# moth_v2_1.net
KiCad netlist of a schematic drawn in EAGLE
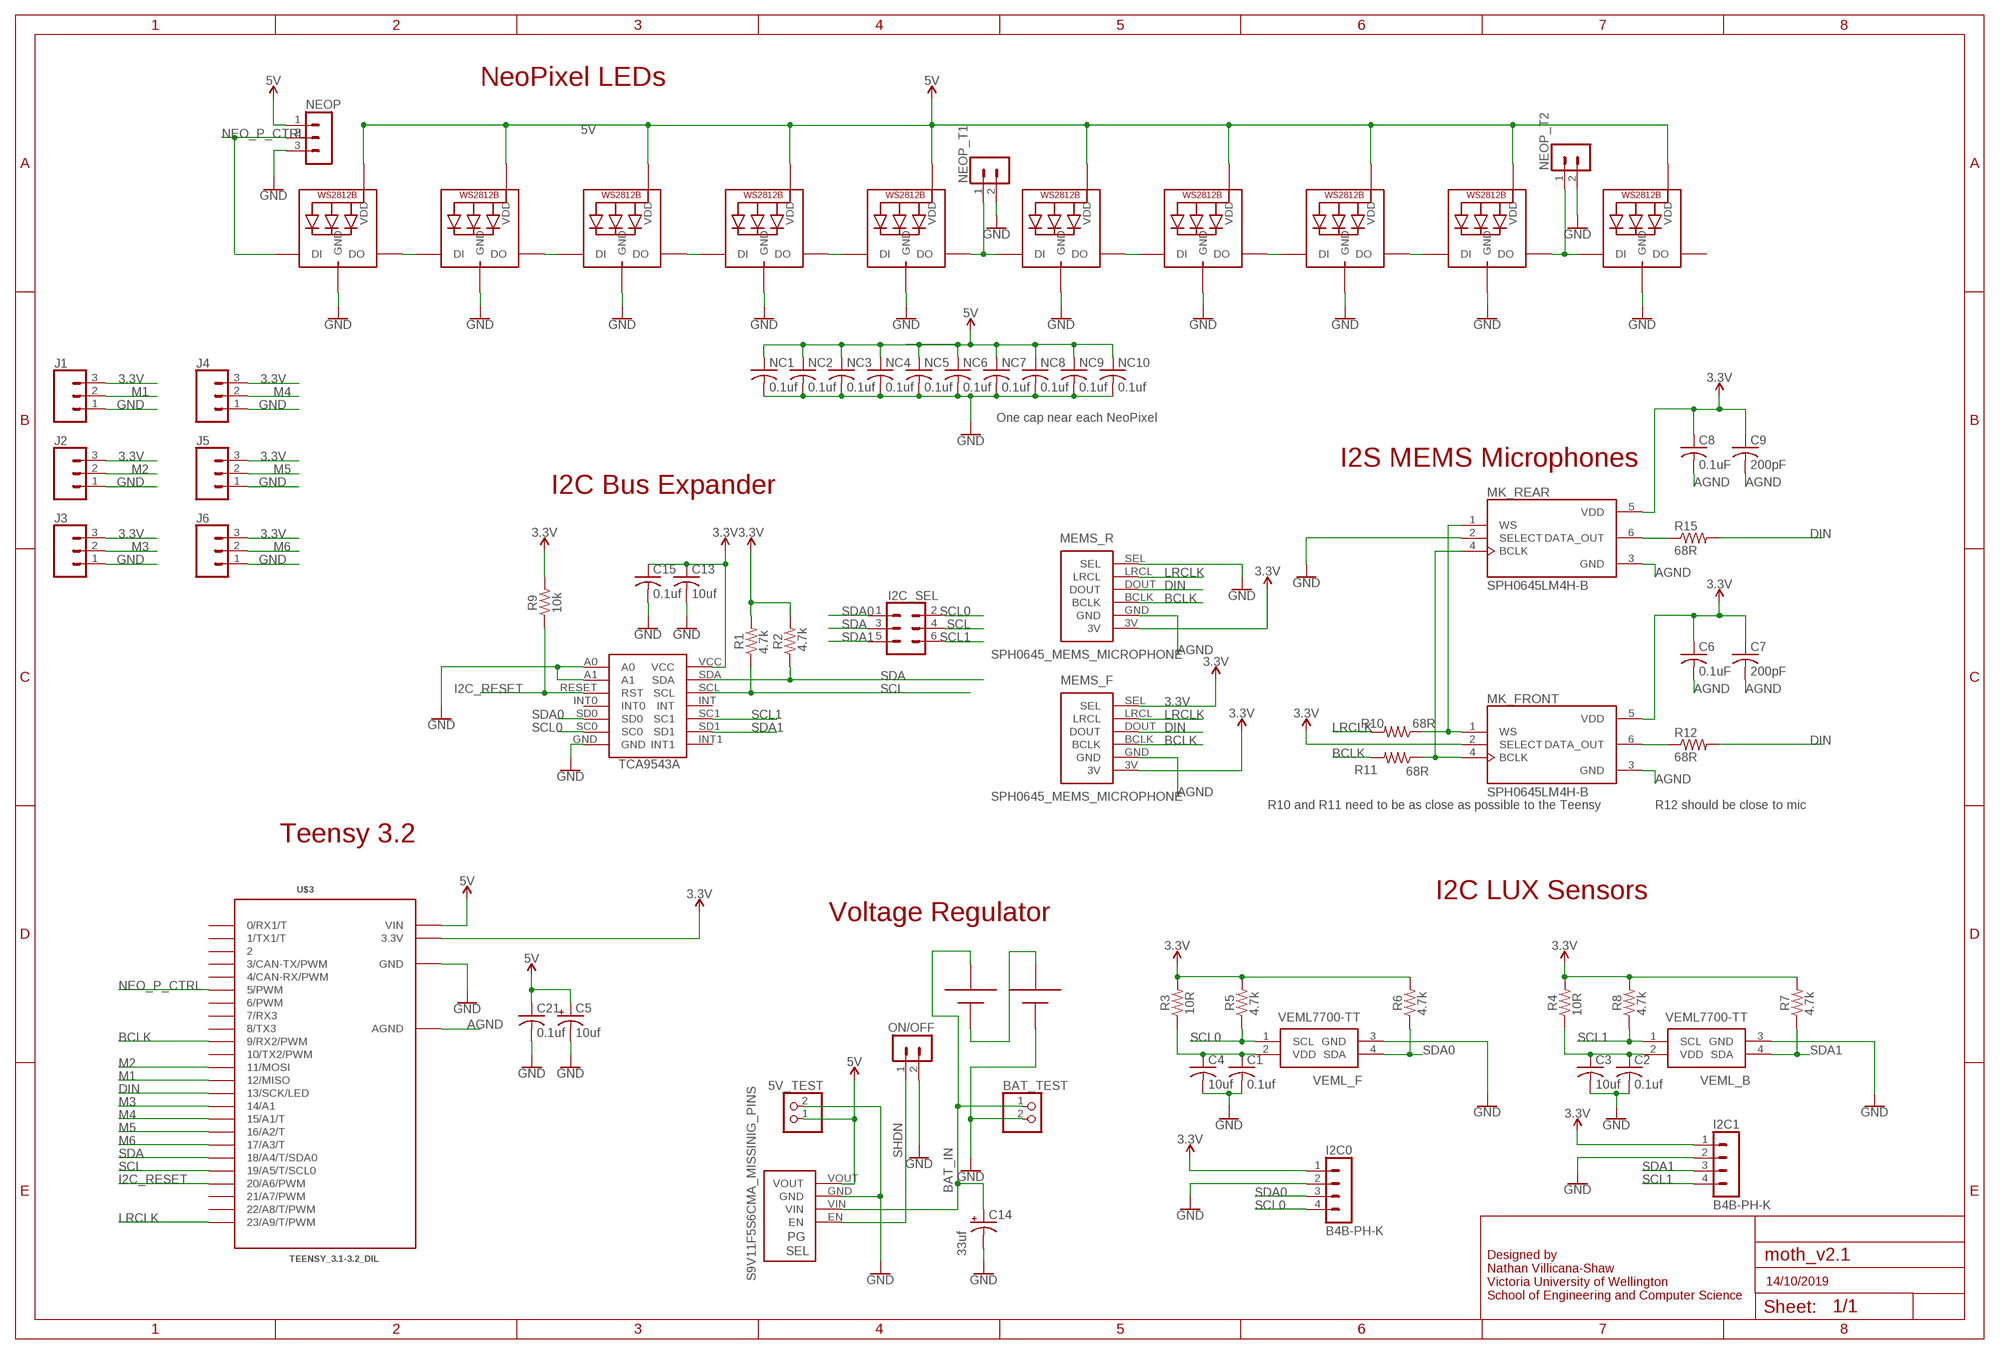
[diagram p0: schematic, sheet 1]

(export (version "E")
  (design (tool "Eeschema 10.0.6"))
  (components
    (comp (ref "5V_TEST")
      (value "PINHD-1X2")
      (footprint "eagle-import:1X02")
      (libsource (lib "eagle-import") (part "PINHD-1X2"))
    )
    (comp (ref "BAT_TEST")
      (value "PINHD-1X2")
      (footprint "eagle-import:1X02")
      (libsource (lib "eagle-import") (part "PINHD-1X2"))
    )
    (comp (ref "C1")
      (value "0.1uf")
      (footprint "eagle-import:C1206K")
      (libsource (lib "eagle-import") (part "C-USC1206K"))
    )
    (comp (ref "C2")
      (value "0.1uf")
      (footprint "eagle-import:C1206K")
      (libsource (lib "eagle-import") (part "C-USC1206K"))
    )
    (comp (ref "C3")
      (value "10uf")
      (footprint "eagle-import:C1206K")
      (libsource (lib "eagle-import") (part "C-USC1206K"))
    )
    (comp (ref "C4")
      (value "10uf")
      (footprint "eagle-import:C1206K")
      (libsource (lib "eagle-import") (part "C-USC1206K"))
    )
    (comp (ref "C5")
      (value "10uf")
      (footprint "eagle-import:E2,5-6")
      (libsource (lib "eagle-import") (part "CPOL-USE2.5-6"))
    )
    (comp (ref "C6")
      (value "0.1uF")
      (footprint "eagle-import:C1206K")
      (libsource (lib "eagle-import") (part "C-USC1206K"))
    )
    (comp (ref "C7")
      (value "200pF")
      (footprint "eagle-import:C1206K")
      (libsource (lib "eagle-import") (part "C-USC1206K"))
    )
    (comp (ref "C8")
      (value "0.1uF")
      (footprint "eagle-import:C1206K")
      (libsource (lib "eagle-import") (part "C-USC1206K"))
    )
    (comp (ref "C9")
      (value "200pF")
      (footprint "eagle-import:C1206K")
      (libsource (lib "eagle-import") (part "C-USC1206K"))
    )
    (comp (ref "C13")
      (value "10uf")
      (footprint "eagle-import:C1206K")
      (libsource (lib "eagle-import") (part "C-USC1206K"))
    )
    (comp (ref "C14")
      (value "33uf")
      (footprint "eagle-import:E2-5")
      (libsource (lib "eagle-import") (part "CPOL-USE2-5"))
    )
    (comp (ref "C15")
      (value "0.1uf")
      (footprint "eagle-import:C1206K")
      (libsource (lib "eagle-import") (part "C-USC1206K"))
    )
    (comp (ref "C21")
      (value "0.1uf")
      (footprint "eagle-import:C1206K")
      (libsource (lib "eagle-import") (part "C-USC1206K"))
    )
    (comp (ref "I2C0")
      (value "B4B-PH-K")
      (footprint "eagle-import:B4B-PH-K")
      (libsource (lib "eagle-import") (part "B4B-PH-K"))
    )
    (comp (ref "I2C1")
      (value "B4B-PH-K")
      (footprint "eagle-import:B4B-PH-K")
      (libsource (lib "eagle-import") (part "B4B-PH-K"))
    )
    (comp (ref "I2C_SEL")
      (value "FEMALE 2x3")
      (footprint "eagle-import:2X3")
      (libsource (lib "eagle-import") (part "CONN_03X2FEMALE"))
    )
    (comp (ref "J1")
      (value "CONN_03")
      (footprint "eagle-import:1X03")
      (libsource (lib "eagle-import") (part "CONN_03"))
    )
    (comp (ref "J2")
      (value "CONN_03")
      (footprint "eagle-import:1X03")
      (libsource (lib "eagle-import") (part "CONN_03"))
    )
    (comp (ref "J3")
      (value "CONN_03")
      (footprint "eagle-import:1X03")
      (libsource (lib "eagle-import") (part "CONN_03"))
    )
    (comp (ref "J4")
      (value "CONN_03")
      (footprint "eagle-import:1X03")
      (libsource (lib "eagle-import") (part "CONN_03"))
    )
    (comp (ref "J5")
      (value "CONN_03")
      (footprint "eagle-import:1X03")
      (libsource (lib "eagle-import") (part "CONN_03"))
    )
    (comp (ref "J6")
      (value "CONN_03")
      (footprint "eagle-import:1X03")
      (libsource (lib "eagle-import") (part "CONN_03"))
    )
    (comp (ref "MEMS_F")
      (value "SPH0645_MEMS_MICROPHONE")
      (footprint "eagle-import:SPH0645")
      (libsource (lib "eagle-import") (part "SPH0645_MEMS_MICROPHONE"))
    )
    (comp (ref "MEMS_R")
      (value "SPH0645_MEMS_MICROPHONE")
      (footprint "eagle-import:SPH0645")
      (libsource (lib "eagle-import") (part "SPH0645_MEMS_MICROPHONE"))
    )
    (comp (ref "MK_FRONT")
      (value "SPH0645LM4H-B")
      (footprint "eagle-import:MIC_SPH0645LM4H-B")
      (fields (field (name "DIGI-KEY_PART_NUMBER") "423-1405-1-ND") (field (name "MF") "Knowles"))
      (libsource (lib "eagle-import") (part "SPH0645LM4H-B"))
    )
    (comp (ref "MK_REAR")
      (value "SPH0645LM4H-B")
      (footprint "eagle-import:MIC_SPH0645LM4H-B")
      (fields (field (name "DIGI-KEY_PART_NUMBER") "423-1405-1-ND") (field (name "MF") "Knowles"))
      (libsource (lib "eagle-import") (part "SPH0645LM4H-B"))
    )
    (comp (ref "NC1")
      (value "0.1uf")
      (footprint "eagle-import:C1206K")
      (libsource (lib "eagle-import") (part "C-USC1206K"))
    )
    (comp (ref "NC2")
      (value "0.1uf")
      (footprint "eagle-import:C1206K")
      (libsource (lib "eagle-import") (part "C-USC1206K"))
    )
    (comp (ref "NC3")
      (value "0.1uf")
      (footprint "eagle-import:C1206K")
      (libsource (lib "eagle-import") (part "C-USC1206K"))
    )
    (comp (ref "NC4")
      (value "0.1uf")
      (footprint "eagle-import:C1206K")
      (libsource (lib "eagle-import") (part "C-USC1206K"))
    )
    (comp (ref "NC5")
      (value "0.1uf")
      (footprint "eagle-import:C1206K")
      (libsource (lib "eagle-import") (part "C-USC1206K"))
    )
    (comp (ref "NC6")
      (value "0.1uf")
      (footprint "eagle-import:C1206K")
      (libsource (lib "eagle-import") (part "C-USC1206K"))
    )
    (comp (ref "NC7")
      (value "0.1uf")
      (footprint "eagle-import:C1206K")
      (libsource (lib "eagle-import") (part "C-USC1206K"))
    )
    (comp (ref "NC8")
      (value "0.1uf")
      (footprint "eagle-import:C1206K")
      (libsource (lib "eagle-import") (part "C-USC1206K"))
    )
    (comp (ref "NC9")
      (value "0.1uf")
      (footprint "eagle-import:C1206K")
      (libsource (lib "eagle-import") (part "C-USC1206K"))
    )
    (comp (ref "NC10")
      (value "0.1uf")
      (footprint "eagle-import:C1206K")
      (libsource (lib "eagle-import") (part "C-USC1206K"))
    )
    (comp (ref "NEO1")
      (value "WS2812B5050")
      (footprint "eagle-import:WS2812B")
      (libsource (lib "eagle-import") (part "WS2812B5050"))
    )
    (comp (ref "NEO2")
      (value "WS2812B5050")
      (footprint "eagle-import:WS2812B")
      (libsource (lib "eagle-import") (part "WS2812B5050"))
    )
    (comp (ref "NEO3")
      (value "WS2812B5050")
      (footprint "eagle-import:WS2812B")
      (libsource (lib "eagle-import") (part "WS2812B5050"))
    )
    (comp (ref "NEO4")
      (value "WS2812B5050")
      (footprint "eagle-import:WS2812B")
      (libsource (lib "eagle-import") (part "WS2812B5050"))
    )
    (comp (ref "NEO5")
      (value "WS2812B5050")
      (footprint "eagle-import:WS2812B")
      (libsource (lib "eagle-import") (part "WS2812B5050"))
    )
    (comp (ref "NEO6")
      (value "WS2812B5050")
      (footprint "eagle-import:WS2812B")
      (libsource (lib "eagle-import") (part "WS2812B5050"))
    )
    (comp (ref "NEO7")
      (value "WS2812B5050")
      (footprint "eagle-import:WS2812B")
      (libsource (lib "eagle-import") (part "WS2812B5050"))
    )
    (comp (ref "NEO8")
      (value "WS2812B5050")
      (footprint "eagle-import:WS2812B")
      (libsource (lib "eagle-import") (part "WS2812B5050"))
    )
    (comp (ref "NEO9")
      (value "WS2812B5050")
      (footprint "eagle-import:WS2812B")
      (libsource (lib "eagle-import") (part "WS2812B5050"))
    )
    (comp (ref "NEO10")
      (value "WS2812B5050")
      (footprint "eagle-import:WS2812B")
      (libsource (lib "eagle-import") (part "WS2812B5050"))
    )
    (comp (ref "NEOP")
      (value "B3B-PH-K")
      (footprint "eagle-import:B3B-PH-K")
      (libsource (lib "eagle-import") (part "B3B-PH-K"))
    )
    (comp (ref "NEOP_T1")
      (value "B2B-PH-K")
      (footprint "eagle-import:B2B-PH-K")
      (libsource (lib "eagle-import") (part "B2B-PH-K"))
    )
    (comp (ref "NEOP_T2")
      (value "B2B-PH-K")
      (footprint "eagle-import:B2B-PH-K")
      (libsource (lib "eagle-import") (part "B2B-PH-K"))
    )
    (comp (ref "ON/OFF")
      (value "B2B-PH-K")
      (footprint "eagle-import:B2B-PH-K")
      (libsource (lib "eagle-import") (part "B2B-PH-K"))
    )
    (comp (ref "R1")
      (value "4.7k")
      (footprint "eagle-import:R1206W")
      (libsource (lib "eagle-import") (part "R-US_R1206W"))
    )
    (comp (ref "R2")
      (value "4.7k")
      (footprint "eagle-import:R1206W")
      (libsource (lib "eagle-import") (part "R-US_R1206W"))
    )
    (comp (ref "R3")
      (value "10R")
      (footprint "eagle-import:R1206W")
      (libsource (lib "eagle-import") (part "R-US_R1206W"))
    )
    (comp (ref "R4")
      (value "10R")
      (footprint "eagle-import:R1206W")
      (libsource (lib "eagle-import") (part "R-US_R1206W"))
    )
    (comp (ref "R5")
      (value "4.7k")
      (footprint "eagle-import:R1206W")
      (libsource (lib "eagle-import") (part "R-US_R1206W"))
    )
    (comp (ref "R6")
      (value "4.7k")
      (footprint "eagle-import:R1206W")
      (libsource (lib "eagle-import") (part "R-US_R1206W"))
    )
    (comp (ref "R7")
      (value "4.7k")
      (footprint "eagle-import:R1206W")
      (libsource (lib "eagle-import") (part "R-US_R1206W"))
    )
    (comp (ref "R8")
      (value "4.7k")
      (footprint "eagle-import:R1206W")
      (libsource (lib "eagle-import") (part "R-US_R1206W"))
    )
    (comp (ref "R9")
      (value "10k")
      (footprint "eagle-import:R1206W")
      (libsource (lib "eagle-import") (part "R-US_R1206W"))
    )
    (comp (ref "R10")
      (value "68R")
      (footprint "eagle-import:M1206")
      (libsource (lib "eagle-import") (part "R-US_M1206"))
    )
    (comp (ref "R11")
      (value "68R")
      (footprint "eagle-import:M1206")
      (libsource (lib "eagle-import") (part "R-US_M1206"))
    )
    (comp (ref "R12")
      (value "68R")
      (footprint "eagle-import:M1206")
      (libsource (lib "eagle-import") (part "R-US_M1206"))
    )
    (comp (ref "R15")
      (value "68R")
      (footprint "eagle-import:M1206")
      (libsource (lib "eagle-import") (part "R-US_M1206"))
    )
    (comp (ref "U$1")
      (value "TCA9543A")
      (footprint "eagle-import:SO14")
      (libsource (lib "eagle-import") (part "TCA9543A"))
    )
    (comp (ref "U$2")
      (value "BK-18650-PC4")
      (footprint "eagle-import:18650-PC4")
      (fields (field (name "MF") "MPD"))
      (libsource (lib "eagle-import") (part "BK-18650-PC4"))
    )
    (comp (ref "U$3")
      (value "TEENSY_3.1-3.2_DIL")
      (footprint "eagle-import:TEENSY_3.0-3.2&LC_DIL")
      (libsource (lib "eagle-import") (part "TEENSY_3.1-3.2_DIL"))
    )
    (comp (ref "U$6")
      (value "S9V11F5S6CMA_MISSINIG_PINS")
      (footprint "eagle-import:S9V11F3S5CMA_MISSING_PINS")
      (libsource (lib "eagle-import") (part "S9V11F5S6CMA_MISSINIG_PINS"))
    )
    (comp (ref "VEML_B")
      (value "VEML7700-TT")
      (footprint "eagle-import:VEML7700")
      (fields (field (name "MOUSER_PART_NUMBER") "78-VEML7700-TT") (field (name "RS_PART_NUMBER") "1226791P"))
      (libsource (lib "eagle-import") (part "VEML7700-TT"))
    )
    (comp (ref "VEML_F")
      (value "VEML7700-TT")
      (footprint "eagle-import:VEML7700")
      (fields (field (name "MOUSER_PART_NUMBER") "78-VEML7700-TT") (field (name "RS_PART_NUMBER") "1226791P"))
      (libsource (lib "eagle-import") (part "VEML7700-TT"))
    )
  )
  (nets
    (net (code "1") (name "/AGND") (class "Default")
      (node (ref "C6") (pin "2") (pinfunction "2_2") (pintype "passive"))
      (node (ref "C7") (pin "2") (pinfunction "2_2") (pintype "passive"))
      (node (ref "C8") (pin "2") (pinfunction "2_2") (pintype "passive"))
      (node (ref "C9") (pin "2") (pinfunction "2_2") (pintype "passive"))
      (node (ref "MEMS_F") (pin "GND") (pinfunction "GND_GND") (pintype "bidirectional"))
      (node (ref "MEMS_R") (pin "GND") (pinfunction "GND_GND") (pintype "bidirectional"))
      (node (ref "MK_FRONT") (pin "3") (pinfunction "GND_3") (pintype "power_in"))
      (node (ref "MK_REAR") (pin "3") (pinfunction "GND_3") (pintype "power_in"))
      (node (ref "U$3") (pin "AGND") (pinfunction "AGND_AGND") (pintype "power_in"))
    )
    (net (code "2") (name "/BAT_IN") (class "Default")
      (node (ref "BAT_TEST") (pin "1") (pinfunction "1_1") (pintype "passive"))
      (node (ref "C14") (pin "+") (pinfunction "+_+") (pintype "passive"))
      (node (ref "U$2") (pin "+1") (pinfunction "+1_+1") (pintype "bidirectional"))
      (node (ref "U$6") (pin "VIN") (pinfunction "VIN_VIN") (pintype "bidirectional"))
    )
    (net (code "3") (name "/BCLK") (class "Default")
      (node (ref "MEMS_F") (pin "BCLK") (pinfunction "BCLK_BCLK") (pintype "bidirectional"))
      (node (ref "MEMS_R") (pin "BCLK") (pinfunction "BCLK_BCLK") (pintype "bidirectional"))
      (node (ref "R11") (pin "2") (pinfunction "2_2") (pintype "passive"))
      (node (ref "U$3") (pin "9") (pinfunction "9/RX2/PWM_9") (pintype "bidirectional"))
    )
    (net (code "4") (name "/DIN") (class "Default")
      (node (ref "MEMS_F") (pin "DOUT") (pinfunction "DOUT_DOUT") (pintype "bidirectional"))
      (node (ref "MEMS_R") (pin "DOUT") (pinfunction "DOUT_DOUT") (pintype "bidirectional"))
      (node (ref "R12") (pin "2") (pinfunction "2_2") (pintype "passive"))
      (node (ref "R15") (pin "2") (pinfunction "2_2") (pintype "passive"))
      (node (ref "U$3") (pin "13") (pinfunction "13/SCK/LED_13") (pintype "bidirectional"))
    )
    (net (code "5") (name "/I2C_RESET") (class "Default")
      (node (ref "R9") (pin "1") (pinfunction "1_1") (pintype "passive"))
      (node (ref "U$1") (pin "RESET") (pinfunction "RST_RESET") (pintype "bidirectional"))
      (node (ref "U$3") (pin "20/A6") (pinfunction "20/A6/PWM_20/A6") (pintype "bidirectional"))
    )
    (net (code "6") (name "/LRCLK") (class "Default")
      (node (ref "MEMS_F") (pin "LRCL") (pinfunction "LRCL_LRCL") (pintype "bidirectional"))
      (node (ref "MEMS_R") (pin "LRCL") (pinfunction "LRCL_LRCL") (pintype "bidirectional"))
      (node (ref "R10") (pin "2") (pinfunction "2_2") (pintype "passive"))
      (node (ref "U$3") (pin "23/A9") (pinfunction "23/A9/T/PWM_23/A9") (pintype "bidirectional"))
    )
    (net (code "7") (name "/M1") (class "Default")
      (node (ref "J1") (pin "2") (pinfunction "2_2") (pintype "passive"))
      (node (ref "U$3") (pin "12") (pinfunction "12/MISO_12") (pintype "bidirectional"))
    )
    (net (code "8") (name "/M2") (class "Default")
      (node (ref "J2") (pin "2") (pinfunction "2_2") (pintype "passive"))
      (node (ref "U$3") (pin "11") (pinfunction "11/MOSI_11") (pintype "bidirectional"))
    )
    (net (code "9") (name "/M3") (class "Default")
      (node (ref "J3") (pin "2") (pinfunction "2_2") (pintype "passive"))
      (node (ref "U$3") (pin "14/A0") (pinfunction "14/A1_14/A0") (pintype "bidirectional"))
    )
    (net (code "10") (name "/M4") (class "Default")
      (node (ref "J4") (pin "2") (pinfunction "2_2") (pintype "passive"))
      (node (ref "U$3") (pin "15/A1") (pinfunction "15/A1/T_15/A1") (pintype "bidirectional"))
    )
    (net (code "11") (name "/M5") (class "Default")
      (node (ref "J5") (pin "2") (pinfunction "2_2") (pintype "passive"))
      (node (ref "U$3") (pin "16/A2") (pinfunction "16/A2/T_16/A2") (pintype "bidirectional"))
    )
    (net (code "12") (name "/M6") (class "Default")
      (node (ref "J6") (pin "2") (pinfunction "2_2") (pintype "passive"))
      (node (ref "U$3") (pin "17/A3") (pinfunction "17/A3/T_17/A3") (pintype "bidirectional"))
    )
    (net (code "13") (name "/NEO_P_CTRL") (class "Default")
      (node (ref "NEO1") (pin "4-DIN") (pinfunction "DI_4-DIN") (pintype "input"))
      (node (ref "NEOP") (pin "2") (pinfunction "2_2") (pintype "passive"))
      (node (ref "U$3") (pin "5") (pinfunction "5/PWM_5") (pintype "bidirectional"))
    )
    (net (code "14") (name "/SCL") (class "Default")
      (node (ref "I2C_SEL") (pin "4") (pinfunction "4_4") (pintype "bidirectional"))
      (node (ref "R1") (pin "1") (pinfunction "1_1") (pintype "passive"))
      (node (ref "U$1") (pin "SCL") (pinfunction "SCL_SCL") (pintype "bidirectional"))
      (node (ref "U$3") (pin "19/A5") (pinfunction "19/A5/T/SCL0_19/A5") (pintype "bidirectional"))
    )
    (net (code "15") (name "/SCL0") (class "Default")
      (node (ref "I2C0") (pin "4") (pinfunction "4_4") (pintype "passive"))
      (node (ref "I2C_SEL") (pin "2") (pinfunction "2_2") (pintype "bidirectional"))
      (node (ref "R5") (pin "1") (pinfunction "1_1") (pintype "passive"))
      (node (ref "U$1") (pin "SC0") (pinfunction "SC0_SC0") (pintype "bidirectional"))
      (node (ref "VEML_F") (pin "1") (pinfunction "SCL_1") (pintype "bidirectional"))
    )
    (net (code "16") (name "/SCL1") (class "Default")
      (node (ref "I2C1") (pin "4") (pinfunction "4_4") (pintype "passive"))
      (node (ref "I2C_SEL") (pin "6") (pinfunction "6_6") (pintype "bidirectional"))
      (node (ref "R8") (pin "1") (pinfunction "1_1") (pintype "passive"))
      (node (ref "U$1") (pin "SC1") (pinfunction "SC1_SC1") (pintype "bidirectional"))
      (node (ref "VEML_B") (pin "1") (pinfunction "SCL_1") (pintype "bidirectional"))
    )
    (net (code "17") (name "/SDA") (class "Default")
      (node (ref "I2C_SEL") (pin "3") (pinfunction "3_3") (pintype "bidirectional"))
      (node (ref "R2") (pin "1") (pinfunction "1_1") (pintype "passive"))
      (node (ref "U$1") (pin "SDA") (pinfunction "SDA_SDA") (pintype "bidirectional"))
      (node (ref "U$3") (pin "18/A4") (pinfunction "18/A4/T/SDA0_18/A4") (pintype "bidirectional"))
    )
    (net (code "18") (name "/SDA0") (class "Default")
      (node (ref "I2C0") (pin "3") (pinfunction "3_3") (pintype "passive"))
      (node (ref "I2C_SEL") (pin "1") (pinfunction "1_1") (pintype "bidirectional"))
      (node (ref "R6") (pin "1") (pinfunction "1_1") (pintype "passive"))
      (node (ref "U$1") (pin "SD0") (pinfunction "SD0_SD0") (pintype "bidirectional"))
      (node (ref "VEML_F") (pin "4") (pinfunction "SDA_4") (pintype "bidirectional"))
    )
    (net (code "19") (name "/SDA1") (class "Default")
      (node (ref "I2C1") (pin "3") (pinfunction "3_3") (pintype "passive"))
      (node (ref "I2C_SEL") (pin "5") (pinfunction "5_5") (pintype "bidirectional"))
      (node (ref "R7") (pin "1") (pinfunction "1_1") (pintype "passive"))
      (node (ref "U$1") (pin "SD1") (pinfunction "SD1_SD1") (pintype "bidirectional"))
      (node (ref "VEML_B") (pin "4") (pinfunction "SDA_4") (pintype "bidirectional"))
    )
    (net (code "20") (name "/SHDN") (class "Default")
      (node (ref "ON/OFF") (pin "1") (pinfunction "1_1") (pintype "passive"))
      (node (ref "U$6") (pin "EN") (pinfunction "EN_EN") (pintype "bidirectional"))
    )
    (net (code "21") (name "3.3V") (class "Default")
      (node (ref "C13") (pin "1") (pinfunction "1_1") (pintype "passive"))
      (node (ref "C15") (pin "1") (pinfunction "1_1") (pintype "passive"))
      (node (ref "C6") (pin "1") (pinfunction "1_1") (pintype "passive"))
      (node (ref "C7") (pin "1") (pinfunction "1_1") (pintype "passive"))
      (node (ref "C8") (pin "1") (pinfunction "1_1") (pintype "passive"))
      (node (ref "C9") (pin "1") (pinfunction "1_1") (pintype "passive"))
      (node (ref "I2C0") (pin "1") (pinfunction "1_1") (pintype "passive"))
      (node (ref "I2C1") (pin "1") (pinfunction "1_1") (pintype "passive"))
      (node (ref "J1") (pin "3") (pinfunction "3_3") (pintype "passive"))
      (node (ref "J2") (pin "3") (pinfunction "3_3") (pintype "passive"))
      (node (ref "J3") (pin "3") (pinfunction "3_3") (pintype "passive"))
      (node (ref "J4") (pin "3") (pinfunction "3_3") (pintype "passive"))
      (node (ref "J5") (pin "3") (pinfunction "3_3") (pintype "passive"))
      (node (ref "J6") (pin "3") (pinfunction "3_3") (pintype "passive"))
      (node (ref "MEMS_F") (pin "3V") (pinfunction "3V_3V") (pintype "bidirectional"))
      (node (ref "MEMS_F") (pin "SEL") (pinfunction "SEL_SEL") (pintype "bidirectional"))
      (node (ref "MEMS_R") (pin "3V") (pinfunction "3V_3V") (pintype "bidirectional"))
      (node (ref "MK_FRONT") (pin "2") (pinfunction "SELECT_2") (pintype "input"))
      (node (ref "MK_FRONT") (pin "5") (pinfunction "VDD_5") (pintype "power_in"))
      (node (ref "MK_REAR") (pin "5") (pinfunction "VDD_5") (pintype "power_in"))
      (node (ref "R1") (pin "2") (pinfunction "2_2") (pintype "passive"))
      (node (ref "R2") (pin "2") (pinfunction "2_2") (pintype "passive"))
      (node (ref "R3") (pin "2") (pinfunction "2_2") (pintype "passive"))
      (node (ref "R4") (pin "2") (pinfunction "2_2") (pintype "passive"))
      (node (ref "R5") (pin "2") (pinfunction "2_2") (pintype "passive"))
      (node (ref "R6") (pin "2") (pinfunction "2_2") (pintype "passive"))
      (node (ref "R7") (pin "2") (pinfunction "2_2") (pintype "passive"))
      (node (ref "R8") (pin "2") (pinfunction "2_2") (pintype "passive"))
      (node (ref "R9") (pin "2") (pinfunction "2_2") (pintype "passive"))
      (node (ref "U$1") (pin "VCC") (pinfunction "VCC_VCC") (pintype "bidirectional"))
      (node (ref "U$3") (pin "3.3V") (pinfunction "3.3V_3.3V") (pintype "power_in"))
    )
    (net (code "22") (name "5V") (class "Default")
      (node (ref "5V_TEST") (pin "1") (pinfunction "1_1") (pintype "passive"))
      (node (ref "C21") (pin "1") (pinfunction "1_1") (pintype "passive"))
      (node (ref "C5") (pin "+") (pinfunction "+_+") (pintype "passive"))
      (node (ref "NC1") (pin "1") (pinfunction "1_1") (pintype "passive"))
      (node (ref "NC10") (pin "1") (pinfunction "1_1") (pintype "passive"))
      (node (ref "NC2") (pin "1") (pinfunction "1_1") (pintype "passive"))
      (node (ref "NC3") (pin "1") (pinfunction "1_1") (pintype "passive"))
      (node (ref "NC4") (pin "1") (pinfunction "1_1") (pintype "passive"))
      (node (ref "NC5") (pin "1") (pinfunction "1_1") (pintype "passive"))
      (node (ref "NC6") (pin "1") (pinfunction "1_1") (pintype "passive"))
      (node (ref "NC7") (pin "1") (pinfunction "1_1") (pintype "passive"))
      (node (ref "NC8") (pin "1") (pinfunction "1_1") (pintype "passive"))
      (node (ref "NC9") (pin "1") (pinfunction "1_1") (pintype "passive"))
      (node (ref "NEO1") (pin "1-VDD") (pinfunction "VDD_1-VDD") (pintype "power_in"))
      (node (ref "NEO10") (pin "1-VDD") (pinfunction "VDD_1-VDD") (pintype "power_in"))
      (node (ref "NEO2") (pin "1-VDD") (pinfunction "VDD_1-VDD") (pintype "power_in"))
      (node (ref "NEO3") (pin "1-VDD") (pinfunction "VDD_1-VDD") (pintype "power_in"))
      (node (ref "NEO4") (pin "1-VDD") (pinfunction "VDD_1-VDD") (pintype "power_in"))
      (node (ref "NEO5") (pin "1-VDD") (pinfunction "VDD_1-VDD") (pintype "power_in"))
      (node (ref "NEO6") (pin "1-VDD") (pinfunction "VDD_1-VDD") (pintype "power_in"))
      (node (ref "NEO7") (pin "1-VDD") (pinfunction "VDD_1-VDD") (pintype "power_in"))
      (node (ref "NEO8") (pin "1-VDD") (pinfunction "VDD_1-VDD") (pintype "power_in"))
      (node (ref "NEO9") (pin "1-VDD") (pinfunction "VDD_1-VDD") (pintype "power_in"))
      (node (ref "NEOP") (pin "1") (pinfunction "1_1") (pintype "passive"))
      (node (ref "U$3") (pin "VIN") (pinfunction "VIN_VIN") (pintype "power_in"))
      (node (ref "U$6") (pin "VOUT") (pinfunction "VOUT_VOUT") (pintype "bidirectional"))
    )
    (net (code "23") (name "GND") (class "Default")
      (node (ref "5V_TEST") (pin "2") (pinfunction "2_2") (pintype "passive"))
      (node (ref "BAT_TEST") (pin "2") (pinfunction "2_2") (pintype "passive"))
      (node (ref "C1") (pin "2") (pinfunction "2_2") (pintype "passive"))
      (node (ref "C13") (pin "2") (pinfunction "2_2") (pintype "passive"))
      (node (ref "C14") (pin "-") (pinfunction "-_-") (pintype "passive"))
      (node (ref "C15") (pin "2") (pinfunction "2_2") (pintype "passive"))
      (node (ref "C2") (pin "2") (pinfunction "2_2") (pintype "passive"))
      (node (ref "C21") (pin "2") (pinfunction "2_2") (pintype "passive"))
      (node (ref "C3") (pin "2") (pinfunction "2_2") (pintype "passive"))
      (node (ref "C4") (pin "2") (pinfunction "2_2") (pintype "passive"))
      (node (ref "C5") (pin "-") (pinfunction "-_-") (pintype "passive"))
      (node (ref "I2C0") (pin "2") (pinfunction "2_2") (pintype "passive"))
      (node (ref "I2C1") (pin "2") (pinfunction "2_2") (pintype "passive"))
      (node (ref "J1") (pin "1") (pinfunction "1_1") (pintype "passive"))
      (node (ref "J2") (pin "1") (pinfunction "1_1") (pintype "passive"))
      (node (ref "J3") (pin "1") (pinfunction "1_1") (pintype "passive"))
      (node (ref "J4") (pin "1") (pinfunction "1_1") (pintype "passive"))
      (node (ref "J5") (pin "1") (pinfunction "1_1") (pintype "passive"))
      (node (ref "J6") (pin "1") (pinfunction "1_1") (pintype "passive"))
      (node (ref "MEMS_R") (pin "SEL") (pinfunction "SEL_SEL") (pintype "bidirectional"))
      (node (ref "MK_REAR") (pin "2") (pinfunction "SELECT_2") (pintype "input"))
      (node (ref "NC1") (pin "2") (pinfunction "2_2") (pintype "passive"))
      (node (ref "NC10") (pin "2") (pinfunction "2_2") (pintype "passive"))
      (node (ref "NC2") (pin "2") (pinfunction "2_2") (pintype "passive"))
      (node (ref "NC3") (pin "2") (pinfunction "2_2") (pintype "passive"))
      (node (ref "NC4") (pin "2") (pinfunction "2_2") (pintype "passive"))
      (node (ref "NC5") (pin "2") (pinfunction "2_2") (pintype "passive"))
      (node (ref "NC6") (pin "2") (pinfunction "2_2") (pintype "passive"))
      (node (ref "NC7") (pin "2") (pinfunction "2_2") (pintype "passive"))
      (node (ref "NC8") (pin "2") (pinfunction "2_2") (pintype "passive"))
      (node (ref "NC9") (pin "2") (pinfunction "2_2") (pintype "passive"))
      (node (ref "NEO1") (pin "3-GND") (pinfunction "GND_3-GND") (pintype "power_in"))
      (node (ref "NEO10") (pin "3-GND") (pinfunction "GND_3-GND") (pintype "power_in"))
      (node (ref "NEO2") (pin "3-GND") (pinfunction "GND_3-GND") (pintype "power_in"))
      (node (ref "NEO3") (pin "3-GND") (pinfunction "GND_3-GND") (pintype "power_in"))
      (node (ref "NEO4") (pin "3-GND") (pinfunction "GND_3-GND") (pintype "power_in"))
      (node (ref "NEO5") (pin "3-GND") (pinfunction "GND_3-GND") (pintype "power_in"))
      (node (ref "NEO6") (pin "3-GND") (pinfunction "GND_3-GND") (pintype "power_in"))
      (node (ref "NEO7") (pin "3-GND") (pinfunction "GND_3-GND") (pintype "power_in"))
      (node (ref "NEO8") (pin "3-GND") (pinfunction "GND_3-GND") (pintype "power_in"))
      (node (ref "NEO9") (pin "3-GND") (pinfunction "GND_3-GND") (pintype "power_in"))
      (node (ref "NEOP") (pin "3") (pinfunction "3_3") (pintype "passive"))
      (node (ref "NEOP_T1") (pin "2") (pinfunction "2_2") (pintype "passive"))
      (node (ref "NEOP_T2") (pin "2") (pinfunction "2_2") (pintype "passive"))
      (node (ref "ON/OFF") (pin "2") (pinfunction "2_2") (pintype "passive"))
      (node (ref "U$1") (pin "A0") (pinfunction "A0_A0") (pintype "bidirectional"))
      (node (ref "U$1") (pin "A1") (pinfunction "A1_A1") (pintype "bidirectional"))
      (node (ref "U$1") (pin "GND") (pinfunction "GND_GND") (pintype "bidirectional"))
      (node (ref "U$2") (pin "-2") (pinfunction "-2_-2") (pintype "bidirectional"))
      (node (ref "U$3") (pin "GND") (pinfunction "GND_GND") (pintype "power_in"))
      (node (ref "U$6") (pin "GND") (pinfunction "GND_GND") (pintype "bidirectional"))
      (node (ref "VEML_B") (pin "3") (pinfunction "GND_3") (pintype "bidirectional"))
      (node (ref "VEML_F") (pin "3") (pinfunction "GND_3") (pintype "bidirectional"))
    )
    (net (code "24") (name "Net-(MK_FRONT-BCLK)") (class "Default")
      (node (ref "MK_FRONT") (pin "4") (pinfunction "BCLK_4") (pintype "input"))
      (node (ref "MK_REAR") (pin "4") (pinfunction "BCLK_4") (pintype "input"))
      (node (ref "R11") (pin "1") (pinfunction "1_1") (pintype "passive"))
    )
    (net (code "25") (name "Net-(MK_FRONT-DATA_OUT)") (class "Default")
      (node (ref "MK_FRONT") (pin "6") (pinfunction "DATA_OUT_6") (pintype "output"))
      (node (ref "R12") (pin "1") (pinfunction "1_1") (pintype "passive"))
    )
    (net (code "26") (name "Net-(MK_FRONT-WS)") (class "Default")
      (node (ref "MK_FRONT") (pin "1") (pinfunction "WS_1") (pintype "input"))
      (node (ref "MK_REAR") (pin "1") (pinfunction "WS_1") (pintype "input"))
      (node (ref "R10") (pin "1") (pinfunction "1_1") (pintype "passive"))
    )
    (net (code "27") (name "Net-(MK_REAR-DATA_OUT)") (class "Default")
      (node (ref "MK_REAR") (pin "6") (pinfunction "DATA_OUT_6") (pintype "output"))
      (node (ref "R15") (pin "1") (pinfunction "1_1") (pintype "passive"))
    )
    (net (code "28") (name "Net-(NEO1-DO)") (class "Default")
      (node (ref "NEO1") (pin "2-DOUT") (pinfunction "DO_2-DOUT") (pintype "output"))
      (node (ref "NEO2") (pin "4-DIN") (pinfunction "DI_4-DIN") (pintype "input"))
    )
    (net (code "29") (name "Net-(NEO2-DO)") (class "Default")
      (node (ref "NEO2") (pin "2-DOUT") (pinfunction "DO_2-DOUT") (pintype "output"))
      (node (ref "NEO3") (pin "4-DIN") (pinfunction "DI_4-DIN") (pintype "input"))
    )
    (net (code "30") (name "Net-(NEO3-DO)") (class "Default")
      (node (ref "NEO3") (pin "2-DOUT") (pinfunction "DO_2-DOUT") (pintype "output"))
      (node (ref "NEO4") (pin "4-DIN") (pinfunction "DI_4-DIN") (pintype "input"))
    )
    (net (code "31") (name "Net-(NEO4-DO)") (class "Default")
      (node (ref "NEO4") (pin "2-DOUT") (pinfunction "DO_2-DOUT") (pintype "output"))
      (node (ref "NEO5") (pin "4-DIN") (pinfunction "DI_4-DIN") (pintype "input"))
    )
    (net (code "32") (name "Net-(NEO5-DO)") (class "Default")
      (node (ref "NEO5") (pin "2-DOUT") (pinfunction "DO_2-DOUT") (pintype "output"))
      (node (ref "NEO6") (pin "4-DIN") (pinfunction "DI_4-DIN") (pintype "input"))
      (node (ref "NEOP_T1") (pin "1") (pinfunction "1_1") (pintype "passive"))
    )
    (net (code "33") (name "Net-(NEO6-DO)") (class "Default")
      (node (ref "NEO6") (pin "2-DOUT") (pinfunction "DO_2-DOUT") (pintype "output"))
      (node (ref "NEO7") (pin "4-DIN") (pinfunction "DI_4-DIN") (pintype "input"))
    )
    (net (code "34") (name "Net-(NEO7-DO)") (class "Default")
      (node (ref "NEO7") (pin "2-DOUT") (pinfunction "DO_2-DOUT") (pintype "output"))
      (node (ref "NEO8") (pin "4-DIN") (pinfunction "DI_4-DIN") (pintype "input"))
    )
    (net (code "35") (name "Net-(NEO8-DO)") (class "Default")
      (node (ref "NEO8") (pin "2-DOUT") (pinfunction "DO_2-DOUT") (pintype "output"))
      (node (ref "NEO9") (pin "4-DIN") (pinfunction "DI_4-DIN") (pintype "input"))
    )
    (net (code "36") (name "Net-(NEO10-DI)") (class "Default")
      (node (ref "NEO10") (pin "4-DIN") (pinfunction "DI_4-DIN") (pintype "input"))
      (node (ref "NEO9") (pin "2-DOUT") (pinfunction "DO_2-DOUT") (pintype "output"))
      (node (ref "NEOP_T2") (pin "1") (pinfunction "1_1") (pintype "passive"))
    )
    (net (code "37") (name "Net-(U$2-Pad+2)") (class "Default")
      (node (ref "U$2") (pin "+2") (pinfunction "+2_+2") (pintype "bidirectional"))
      (node (ref "U$2") (pin "-1") (pinfunction "-1_-1") (pintype "bidirectional"))
    )
    (net (code "38") (name "Net-(VEML_B-VDD)") (class "Default")
      (node (ref "C2") (pin "1") (pinfunction "1_1") (pintype "passive"))
      (node (ref "C3") (pin "1") (pinfunction "1_1") (pintype "passive"))
      (node (ref "R4") (pin "1") (pinfunction "1_1") (pintype "passive"))
      (node (ref "VEML_B") (pin "2") (pinfunction "VDD_2") (pintype "bidirectional"))
    )
    (net (code "39") (name "Net-(VEML_F-VDD)") (class "Default")
      (node (ref "C1") (pin "1") (pinfunction "1_1") (pintype "passive"))
      (node (ref "C4") (pin "1") (pinfunction "1_1") (pintype "passive"))
      (node (ref "R3") (pin "1") (pinfunction "1_1") (pintype "passive"))
      (node (ref "VEML_F") (pin "2") (pinfunction "VDD_2") (pintype "bidirectional"))
    )
    (net (code "40") (name "unconnected-(NEO10-DO-Pad2-DOUT)") (class "Default")
      (node (ref "NEO10") (pin "2-DOUT") (pinfunction "DO_2-DOUT") (pintype "output"))
    )
    (net (code "41") (name "unconnected-(U$1-PadINT)") (class "Default")
      (node (ref "U$1") (pin "INT") (pinfunction "INT_INT") (pintype "bidirectional"))
    )
    (net (code "42") (name "unconnected-(U$1-PadINT0)") (class "Default")
      (node (ref "U$1") (pin "INT0") (pinfunction "INT0_INT0") (pintype "bidirectional"))
    )
    (net (code "43") (name "unconnected-(U$1-PadINT1)") (class "Default")
      (node (ref "U$1") (pin "INT1") (pinfunction "INT1_INT1") (pintype "bidirectional"))
    )
    (net (code "44") (name "unconnected-(U$3-0{slash}RX1{slash}T-Pad0)") (class "Default")
      (node (ref "U$3") (pin "0") (pinfunction "0/RX1/T_0") (pintype "bidirectional"))
    )
    (net (code "45") (name "unconnected-(U$3-1{slash}TX1{slash}T-Pad1)") (class "Default")
      (node (ref "U$3") (pin "1") (pinfunction "1/TX1/T_1") (pintype "bidirectional"))
    )
    (net (code "46") (name "unconnected-(U$3-3{slash}CAN-TX{slash}PWM-Pad3)") (class "Default")
      (node (ref "U$3") (pin "3") (pinfunction "3/CAN-TX/PWM_3") (pintype "bidirectional"))
    )
    (net (code "47") (name "unconnected-(U$3-4{slash}CAN-RX{slash}PWM-Pad4)") (class "Default")
      (node (ref "U$3") (pin "4") (pinfunction "4/CAN-RX/PWM_4") (pintype "bidirectional"))
    )
    (net (code "48") (name "unconnected-(U$3-6{slash}PWM-Pad6)") (class "Default")
      (node (ref "U$3") (pin "6") (pinfunction "6/PWM_6") (pintype "bidirectional"))
    )
    (net (code "49") (name "unconnected-(U$3-7{slash}RX3-Pad7)") (class "Default")
      (node (ref "U$3") (pin "7") (pinfunction "7/RX3_7") (pintype "bidirectional"))
    )
    (net (code "50") (name "unconnected-(U$3-8{slash}TX3-Pad8)") (class "Default")
      (node (ref "U$3") (pin "8") (pinfunction "8/TX3_8") (pintype "bidirectional"))
    )
    (net (code "51") (name "unconnected-(U$3-10{slash}TX2{slash}PWM-Pad10)") (class "Default")
      (node (ref "U$3") (pin "10") (pinfunction "10/TX2/PWM_10") (pintype "bidirectional"))
    )
    (net (code "52") (name "unconnected-(U$3-21{slash}A7{slash}PWM-Pad21{slash}A7)") (class "Default")
      (node (ref "U$3") (pin "21/A7") (pinfunction "21/A7/PWM_21/A7") (pintype "bidirectional"))
    )
    (net (code "53") (name "unconnected-(U$3-22{slash}A8{slash}T{slash}PWM-Pad22{slash}A8)") (class "Default")
      (node (ref "U$3") (pin "22/A8") (pinfunction "22/A8/T/PWM_22/A8") (pintype "bidirectional"))
    )
    (net (code "54") (name "unconnected-(U$3-Pad2)") (class "Default")
      (node (ref "U$3") (pin "2") (pinfunction "2_2") (pintype "bidirectional"))
    )
  )
)
